# MARK.net
KiCad netlist of a schematic drawn in EAGLE
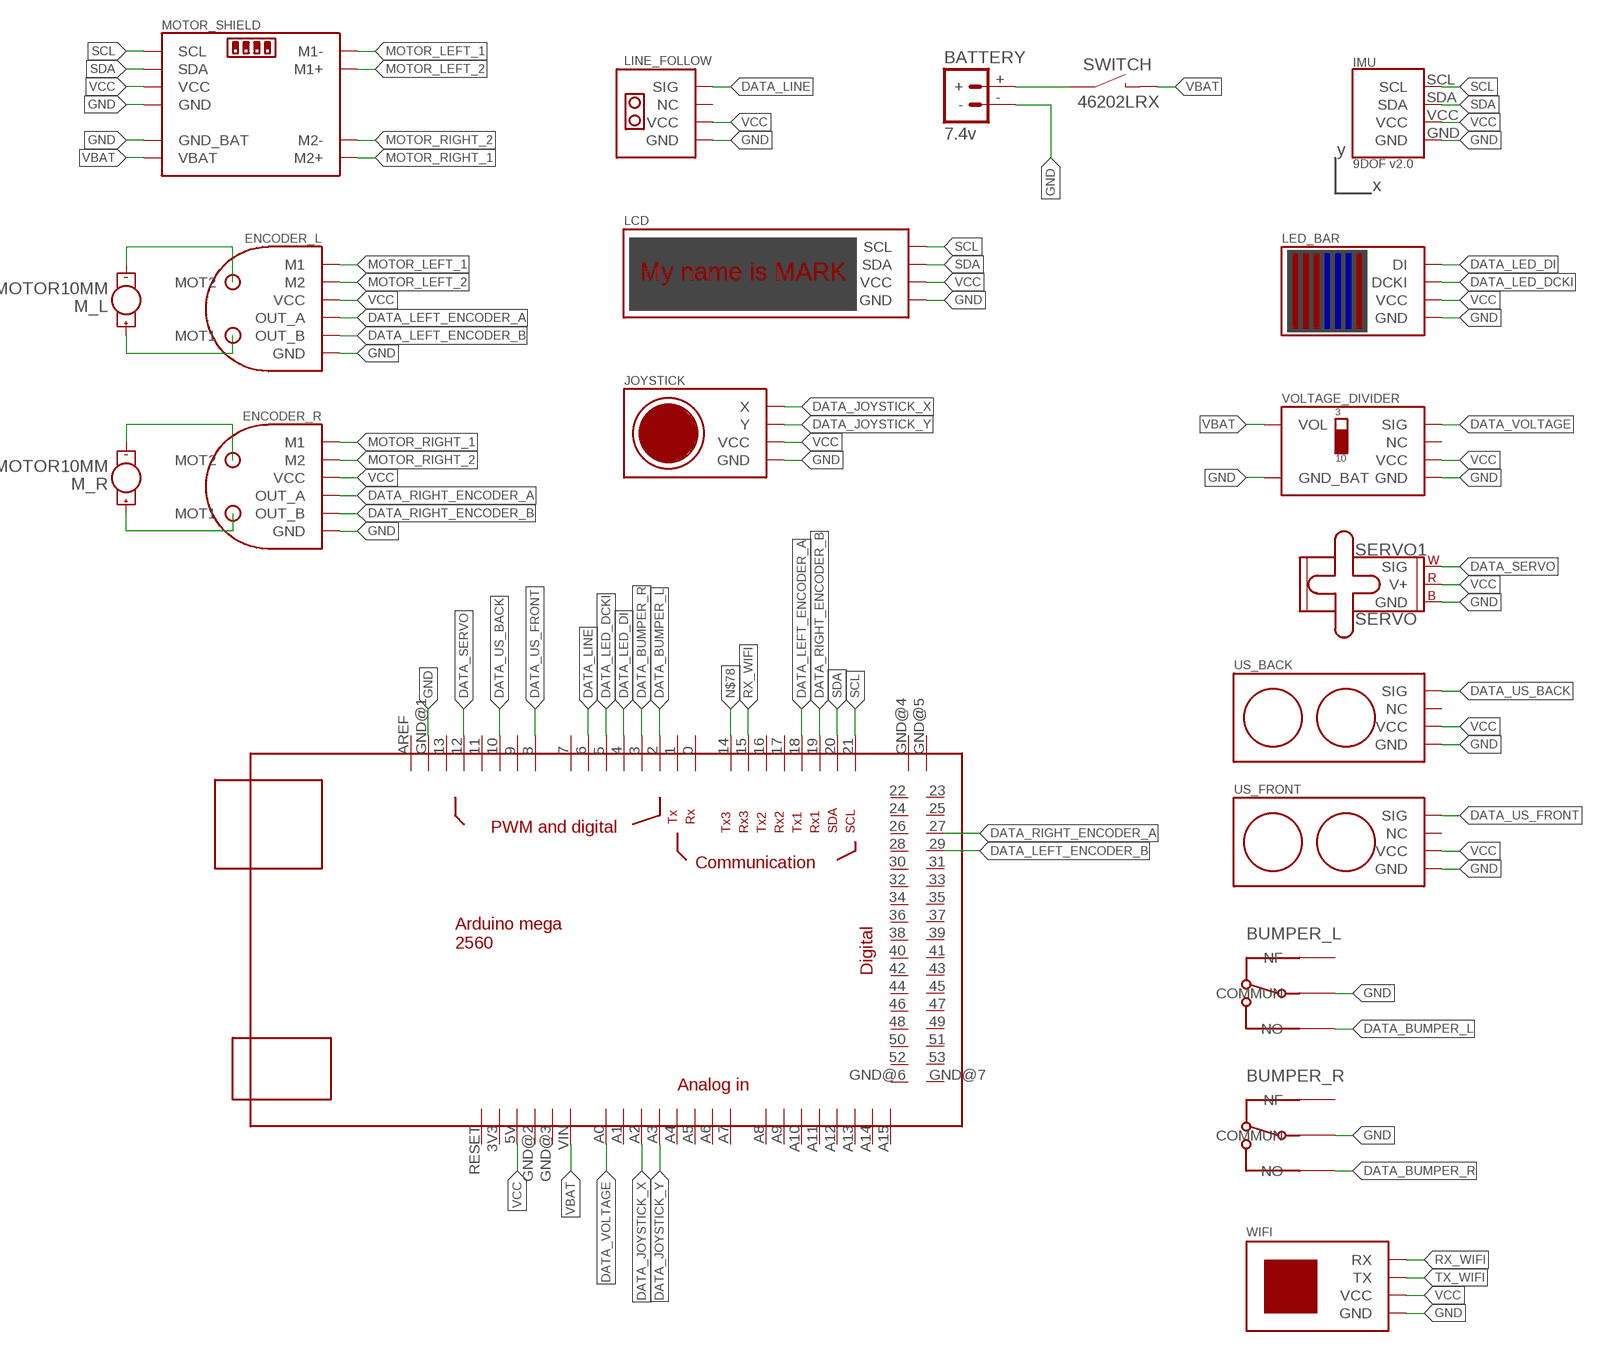
[diagram p0: schematic, sheet 1]

(export (version "E")
  (design (tool "Eeschema 10.0.6"))
  (components
    (comp (ref "BATTERY")
      (value "7.4v")
      (footprint "eagle-import:DEANS")
      (libsource (lib "eagle-import") (part "BATTERY_CONN_DEANS"))
    )
    (comp (ref "BUMPER_L")
      (value "MICROSWITCHCOUDE")
      (footprint "eagle-import:DG23-B3RA")
      (libsource (lib "eagle-import") (part "MICROSWITCHCOUDE"))
    )
    (comp (ref "BUMPER_R")
      (value "MICROSWITCHCOUDE")
      (footprint "eagle-import:DG23-B3RA")
      (libsource (lib "eagle-import") (part "MICROSWITCHCOUDE"))
    )
    (comp (ref "ENCODER_L")
      (value "MOTOR")
      (footprint "eagle-import:MOTOR")
      (libsource (lib "eagle-import") (part "MOTOR"))
    )
    (comp (ref "ENCODER_R")
      (value "MOTOR")
      (footprint "eagle-import:MOTOR")
      (libsource (lib "eagle-import") (part "MOTOR"))
    )
    (comp (ref "IMU")
      (value "IMU")
      (footprint "eagle-import:IMU")
      (libsource (lib "eagle-import") (part "IMU"))
    )
    (comp (ref "JOYSTICK")
      (value "JOYSTICK")
      (footprint "eagle-import:JOYSTICK")
      (libsource (lib "eagle-import") (part "JOYSTICK"))
    )
    (comp (ref "LCD")
      (value "LCD")
      (footprint "eagle-import:LCD")
      (libsource (lib "eagle-import") (part "LCD"))
    )
    (comp (ref "LED_BAR")
      (value "LED_BAR")
      (footprint "eagle-import:LED_BAR")
      (libsource (lib "eagle-import") (part "LED_BAR"))
    )
    (comp (ref "LINE_FOLLOW")
      (value "INFRARED")
      (footprint "eagle-import:INFRARED")
      (libsource (lib "eagle-import") (part "INFRARED"))
    )
    (comp (ref "MOTOR_SHIELD")
      (value "MOTOR_SHIELD")
      (footprint "eagle-import:MOTOR_SHIELD")
      (libsource (lib "eagle-import") (part "MOTOR_SHIELD"))
    )
    (comp (ref "M_L")
      (value "MOTOR10MM")
      (footprint "eagle-import:VIBE-MOTOR-10MM")
      (libsource (lib "eagle-import") (part "MOTOR10MM"))
    )
    (comp (ref "M_R")
      (value "MOTOR10MM")
      (footprint "eagle-import:VIBE-MOTOR-10MM")
      (libsource (lib "eagle-import") (part "MOTOR10MM"))
    )
    (comp (ref "SERVO1")
      (value "SERVO")
      (footprint "eagle-import:1X03")
      (libsource (lib "eagle-import") (part "SERVO"))
    )
    (comp (ref "SWITCH")
      (value "46202LRX")
      (footprint "eagle-import:46202LRX")
      (libsource (lib "eagle-import") (part "46202LRX"))
    )
    (comp (ref "U$11")
      (value "MEGA_DEVICE")
      (footprint "eagle-import:MEGAOUTLINE")
      (libsource (lib "eagle-import") (part "MEGA_DEVICE"))
    )
    (comp (ref "US_BACK")
      (value "ULTRASONIC")
      (footprint "eagle-import:ULTRASONIC")
      (libsource (lib "eagle-import") (part "ULTRASONIC"))
    )
    (comp (ref "US_FRONT")
      (value "ULTRASONIC")
      (footprint "eagle-import:ULTRASONIC")
      (libsource (lib "eagle-import") (part "ULTRASONIC"))
    )
    (comp (ref "VOLTAGE_DIVIDER")
      (value "VOLTAGE_DIVIDER")
      (footprint "eagle-import:VOLTAGE_DIVIDER")
      (libsource (lib "eagle-import") (part "VOLTAGE_DIVIDER"))
    )
    (comp (ref "WIFI")
      (value "WIFI")
      (footprint "eagle-import:WIFI")
      (libsource (lib "eagle-import") (part "WIFI"))
    )
  )
  (nets
    (net (code "1") (name "DATA_BUMPER_L") (class "Default")
      (node (ref "BUMPER_L") (pin "NO") (pinfunction "NO_NO") (pintype "bidirectional"))
      (node (ref "U$11") (pin "2") (pinfunction "2_2") (pintype "bidirectional"))
    )
    (net (code "2") (name "DATA_BUMPER_R") (class "Default")
      (node (ref "BUMPER_R") (pin "NO") (pinfunction "NO_NO") (pintype "bidirectional"))
      (node (ref "U$11") (pin "3") (pinfunction "3_3") (pintype "bidirectional"))
    )
    (net (code "3") (name "DATA_JOYSTICK_X") (class "Default")
      (node (ref "JOYSTICK") (pin "X") (pinfunction "X_X") (pintype "output"))
      (node (ref "U$11") (pin "A2") (pinfunction "A2_A2") (pintype "bidirectional"))
    )
    (net (code "4") (name "DATA_JOYSTICK_Y") (class "Default")
      (node (ref "JOYSTICK") (pin "Y") (pinfunction "Y_Y") (pintype "output"))
      (node (ref "U$11") (pin "A3") (pinfunction "A3_A3") (pintype "bidirectional"))
    )
    (net (code "5") (name "DATA_LED_DCKI") (class "Default")
      (node (ref "LED_BAR") (pin "DCKI") (pinfunction "DCKI_DCKI") (pintype "bidirectional"))
      (node (ref "U$11") (pin "5") (pinfunction "5_5") (pintype "bidirectional"))
    )
    (net (code "6") (name "DATA_LED_DI") (class "Default")
      (node (ref "LED_BAR") (pin "DI") (pinfunction "DI_DI") (pintype "bidirectional"))
      (node (ref "U$11") (pin "4") (pinfunction "4_4") (pintype "bidirectional"))
    )
    (net (code "7") (name "DATA_LEFT_ENCODER_A") (class "Default")
      (node (ref "ENCODER_L") (pin "OUT_A") (pinfunction "OUT_A_OUT_A") (pintype "bidirectional"))
      (node (ref "U$11") (pin "18") (pinfunction "18_18") (pintype "bidirectional"))
    )
    (net (code "8") (name "DATA_LEFT_ENCODER_B") (class "Default")
      (node (ref "ENCODER_L") (pin "OUT_B") (pinfunction "OUT_B_OUT_B") (pintype "bidirectional"))
      (node (ref "U$11") (pin "29") (pinfunction "29_29") (pintype "bidirectional"))
    )
    (net (code "9") (name "DATA_LINE") (class "Default")
      (node (ref "LINE_FOLLOW") (pin "SIG") (pinfunction "SIG_SIG") (pintype "bidirectional"))
      (node (ref "U$11") (pin "6") (pinfunction "6_6") (pintype "bidirectional"))
    )
    (net (code "10") (name "DATA_RIGHT_ENCODER_A") (class "Default")
      (node (ref "ENCODER_R") (pin "OUT_A") (pinfunction "OUT_A_OUT_A") (pintype "bidirectional"))
      (node (ref "U$11") (pin "27") (pinfunction "27_27") (pintype "bidirectional"))
    )
    (net (code "11") (name "DATA_RIGHT_ENCODER_B") (class "Default")
      (node (ref "ENCODER_R") (pin "OUT_B") (pinfunction "OUT_B_OUT_B") (pintype "bidirectional"))
      (node (ref "U$11") (pin "19") (pinfunction "19_19") (pintype "bidirectional"))
    )
    (net (code "12") (name "DATA_SERVO") (class "Default")
      (node (ref "SERVO1") (pin "1") (pinfunction "SIG_1") (pintype "bidirectional"))
      (node (ref "U$11") (pin "12") (pinfunction "12_12") (pintype "bidirectional"))
    )
    (net (code "13") (name "DATA_US_BACK") (class "Default")
      (node (ref "U$11") (pin "10") (pinfunction "10_10") (pintype "bidirectional"))
      (node (ref "US_BACK") (pin "SIG") (pinfunction "SIG_SIG") (pintype "bidirectional"))
    )
    (net (code "14") (name "DATA_US_FRONT") (class "Default")
      (node (ref "U$11") (pin "8") (pinfunction "8_8") (pintype "bidirectional"))
      (node (ref "US_FRONT") (pin "SIG") (pinfunction "SIG_SIG") (pintype "bidirectional"))
    )
    (net (code "15") (name "DATA_VOLTAGE") (class "Default")
      (node (ref "U$11") (pin "A0") (pinfunction "A0_A0") (pintype "bidirectional"))
      (node (ref "VOLTAGE_DIVIDER") (pin "3") (pinfunction "SIG_3") (pintype "bidirectional"))
    )
    (net (code "16") (name "GND") (class "Default")
      (node (ref "BATTERY") (pin "-") (pinfunction "-_-") (pintype "passive"))
      (node (ref "BUMPER_L") (pin "COMMUN") (pinfunction "COMMUN_COMMUN") (pintype "bidirectional"))
      (node (ref "BUMPER_R") (pin "COMMUN") (pinfunction "COMMUN_COMMUN") (pintype "bidirectional"))
      (node (ref "ENCODER_L") (pin "GND") (pinfunction "GND_GND") (pintype "bidirectional"))
      (node (ref "ENCODER_R") (pin "GND") (pinfunction "GND_GND") (pintype "bidirectional"))
      (node (ref "IMU") (pin "GND") (pinfunction "GND_GND") (pintype "bidirectional"))
      (node (ref "JOYSTICK") (pin "GND") (pinfunction "GND_GND") (pintype "power_in"))
      (node (ref "LCD") (pin "GND") (pinfunction "GND_GND") (pintype "bidirectional"))
      (node (ref "LED_BAR") (pin "GND") (pinfunction "GND_GND") (pintype "bidirectional"))
      (node (ref "LINE_FOLLOW") (pin "GND") (pinfunction "GND_GND") (pintype "bidirectional"))
      (node (ref "MOTOR_SHIELD") (pin "GND") (pinfunction "GND_GND") (pintype "bidirectional"))
      (node (ref "MOTOR_SHIELD") (pin "GND_BAT") (pinfunction "GND_BAT_GND_BAT") (pintype "bidirectional"))
      (node (ref "SERVO1") (pin "3") (pinfunction "GND_3") (pintype "bidirectional"))
      (node (ref "U$11") (pin "GND@1") (pinfunction "GND_GND@1") (pintype "bidirectional"))
      (node (ref "US_BACK") (pin "GND") (pinfunction "GND_GND") (pintype "bidirectional"))
      (node (ref "US_FRONT") (pin "GND") (pinfunction "GND_GND") (pintype "bidirectional"))
      (node (ref "VOLTAGE_DIVIDER") (pin "2") (pinfunction "GND_BAT_2") (pintype "bidirectional"))
      (node (ref "VOLTAGE_DIVIDER") (pin "6") (pinfunction "GND_6") (pintype "bidirectional"))
      (node (ref "WIFI") (pin "GND") (pinfunction "GND_GND") (pintype "bidirectional"))
    )
    (net (code "17") (name "MOTOR_LEFT_1") (class "Default")
      (node (ref "ENCODER_L") (pin "M1") (pinfunction "M1_M1") (pintype "bidirectional"))
      (node (ref "MOTOR_SHIELD") (pin "M1-") (pinfunction "M1-_M1-") (pintype "bidirectional"))
    )
    (net (code "18") (name "MOTOR_LEFT_2") (class "Default")
      (node (ref "ENCODER_L") (pin "M2") (pinfunction "M2_M2") (pintype "bidirectional"))
      (node (ref "MOTOR_SHIELD") (pin "M1+") (pinfunction "M1+_M1+") (pintype "bidirectional"))
    )
    (net (code "19") (name "MOTOR_RIGHT_1") (class "Default")
      (node (ref "ENCODER_R") (pin "M1") (pinfunction "M1_M1") (pintype "bidirectional"))
      (node (ref "MOTOR_SHIELD") (pin "M2+") (pinfunction "M2+_M2+") (pintype "bidirectional"))
    )
    (net (code "20") (name "MOTOR_RIGHT_2") (class "Default")
      (node (ref "ENCODER_R") (pin "M2") (pinfunction "M2_M2") (pintype "bidirectional"))
      (node (ref "MOTOR_SHIELD") (pin "M2-") (pinfunction "M2-_M2-") (pintype "bidirectional"))
    )
    (net (code "21") (name "N$78") (class "Default")
      (node (ref "U$11") (pin "14") (pinfunction "14_14") (pintype "bidirectional"))
    )
    (net (code "22") (name "Net-(ENCODER_L-PadMOT1)") (class "Default")
      (node (ref "ENCODER_L") (pin "MOT1") (pinfunction "MOT1_MOT1") (pintype "bidirectional"))
      (node (ref "M_L") (pin "+") (pinfunction "+_+") (pintype "bidirectional"))
    )
    (net (code "23") (name "Net-(ENCODER_L-PadMOT2)") (class "Default")
      (node (ref "ENCODER_L") (pin "MOT2") (pinfunction "MOT2_MOT2") (pintype "bidirectional"))
      (node (ref "M_L") (pin "-") (pinfunction "-_-") (pintype "bidirectional"))
    )
    (net (code "24") (name "Net-(ENCODER_R-PadMOT1)") (class "Default")
      (node (ref "ENCODER_R") (pin "MOT1") (pinfunction "MOT1_MOT1") (pintype "bidirectional"))
      (node (ref "M_R") (pin "+") (pinfunction "+_+") (pintype "bidirectional"))
    )
    (net (code "25") (name "Net-(ENCODER_R-PadMOT2)") (class "Default")
      (node (ref "ENCODER_R") (pin "MOT2") (pinfunction "MOT2_MOT2") (pintype "bidirectional"))
      (node (ref "M_R") (pin "-") (pinfunction "-_-") (pintype "bidirectional"))
    )
    (net (code "26") (name "Net-(SWITCH-A1)") (class "Default")
      (node (ref "BATTERY") (pin "+") (pinfunction "+_+") (pintype "passive"))
      (node (ref "SWITCH") (pin "P$1") (pinfunction "A1_P$1") (pintype "passive"))
    )
    (net (code "27") (name "RX_WIFI") (class "Default")
      (node (ref "U$11") (pin "15") (pinfunction "15_15") (pintype "bidirectional"))
      (node (ref "WIFI") (pin "RX") (pinfunction "RX_RX") (pintype "bidirectional"))
    )
    (net (code "28") (name "SCL") (class "Default")
      (node (ref "IMU") (pin "SCL") (pinfunction "SCL_SCL") (pintype "bidirectional"))
      (node (ref "LCD") (pin "SCL") (pinfunction "SCL_SCL") (pintype "bidirectional"))
      (node (ref "MOTOR_SHIELD") (pin "SCL") (pinfunction "SCL_SCL") (pintype "bidirectional"))
      (node (ref "U$11") (pin "21") (pinfunction "21_21") (pintype "bidirectional"))
    )
    (net (code "29") (name "SDA") (class "Default")
      (node (ref "IMU") (pin "SDA") (pinfunction "SDA_SDA") (pintype "bidirectional"))
      (node (ref "LCD") (pin "SDA") (pinfunction "SDA_SDA") (pintype "bidirectional"))
      (node (ref "MOTOR_SHIELD") (pin "SDA") (pinfunction "SDA_SDA") (pintype "bidirectional"))
      (node (ref "U$11") (pin "20") (pinfunction "20_20") (pintype "bidirectional"))
    )
    (net (code "30") (name "TX_WIFI") (class "Default")
      (node (ref "WIFI") (pin "TX") (pinfunction "TX_TX") (pintype "bidirectional"))
    )
    (net (code "31") (name "VBAT") (class "Default")
      (node (ref "MOTOR_SHIELD") (pin "VBAT") (pinfunction "VBAT_VBAT") (pintype "bidirectional"))
      (node (ref "SWITCH") (pin "P$2") (pinfunction "B_P$2") (pintype "passive"))
      (node (ref "U$11") (pin "VIN") (pinfunction "VIN_VIN") (pintype "bidirectional"))
      (node (ref "VOLTAGE_DIVIDER") (pin "1") (pinfunction "VOL_1") (pintype "bidirectional"))
    )
    (net (code "32") (name "VCC") (class "Default")
      (node (ref "ENCODER_L") (pin "VCC") (pinfunction "VCC_VCC") (pintype "bidirectional"))
      (node (ref "ENCODER_R") (pin "VCC") (pinfunction "VCC_VCC") (pintype "bidirectional"))
      (node (ref "IMU") (pin "VCC") (pinfunction "VCC_VCC") (pintype "bidirectional"))
      (node (ref "JOYSTICK") (pin "VCC") (pinfunction "VCC_VCC") (pintype "power_in"))
      (node (ref "LCD") (pin "VCC") (pinfunction "VCC_VCC") (pintype "bidirectional"))
      (node (ref "LED_BAR") (pin "VCC") (pinfunction "VCC_VCC") (pintype "bidirectional"))
      (node (ref "LINE_FOLLOW") (pin "VCC") (pinfunction "VCC_VCC") (pintype "bidirectional"))
      (node (ref "MOTOR_SHIELD") (pin "VCC") (pinfunction "VCC_VCC") (pintype "bidirectional"))
      (node (ref "SERVO1") (pin "2") (pinfunction "V+_2") (pintype "bidirectional"))
      (node (ref "U$11") (pin "5V") (pinfunction "5V_5V") (pintype "bidirectional"))
      (node (ref "US_BACK") (pin "VCC") (pinfunction "VCC_VCC") (pintype "bidirectional"))
      (node (ref "US_FRONT") (pin "VCC") (pinfunction "VCC_VCC") (pintype "bidirectional"))
      (node (ref "VOLTAGE_DIVIDER") (pin "5") (pinfunction "VCC_5") (pintype "bidirectional"))
      (node (ref "WIFI") (pin "VCC") (pinfunction "VCC_VCC") (pintype "bidirectional"))
    )
    (net (code "33") (name "unconnected-(BUMPER_L-PadNF)") (class "Default")
      (node (ref "BUMPER_L") (pin "NF") (pinfunction "NF_NF") (pintype "bidirectional"))
    )
    (net (code "34") (name "unconnected-(BUMPER_R-PadNF)") (class "Default")
      (node (ref "BUMPER_R") (pin "NF") (pinfunction "NF_NF") (pintype "bidirectional"))
    )
    (net (code "35") (name "unconnected-(LINE_FOLLOW-PadNC)") (class "Default")
      (node (ref "LINE_FOLLOW") (pin "NC") (pinfunction "NC_NC") (pintype "bidirectional"))
    )
    (net (code "36") (name "unconnected-(U$11-GND-PadGND@2)") (class "Default")
      (node (ref "U$11") (pin "GND@2") (pinfunction "GND_GND@2") (pintype "bidirectional"))
    )
    (net (code "37") (name "unconnected-(U$11-GND-PadGND@3)") (class "Default")
      (node (ref "U$11") (pin "GND@3") (pinfunction "GND_GND@3") (pintype "bidirectional"))
    )
    (net (code "38") (name "unconnected-(U$11-GND-PadGND@4)") (class "Default")
      (node (ref "U$11") (pin "GND@4") (pinfunction "GND_GND@4") (pintype "bidirectional"))
    )
    (net (code "39") (name "unconnected-(U$11-GND-PadGND@5)") (class "Default")
      (node (ref "U$11") (pin "GND@5") (pinfunction "GND_GND@5") (pintype "bidirectional"))
    )
    (net (code "40") (name "unconnected-(U$11-GND-PadGND@6)") (class "Default")
      (node (ref "U$11") (pin "GND@6") (pinfunction "GND_GND@6") (pintype "bidirectional"))
    )
    (net (code "41") (name "unconnected-(U$11-GND-PadGND@7)") (class "Default")
      (node (ref "U$11") (pin "GND@7") (pinfunction "GND_GND@7") (pintype "bidirectional"))
    )
    (net (code "42") (name "unconnected-(U$11-Pad0)") (class "Default")
      (node (ref "U$11") (pin "0") (pinfunction "0_0") (pintype "bidirectional"))
    )
    (net (code "43") (name "unconnected-(U$11-Pad1)") (class "Default")
      (node (ref "U$11") (pin "1") (pinfunction "1_1") (pintype "bidirectional"))
    )
    (net (code "44") (name "unconnected-(U$11-Pad3V3)") (class "Default")
      (node (ref "U$11") (pin "3V3") (pinfunction "3V3_3V3") (pintype "bidirectional"))
    )
    (net (code "45") (name "unconnected-(U$11-Pad7)") (class "Default")
      (node (ref "U$11") (pin "7") (pinfunction "7_7") (pintype "bidirectional"))
    )
    (net (code "46") (name "unconnected-(U$11-Pad9)") (class "Default")
      (node (ref "U$11") (pin "9") (pinfunction "9_9") (pintype "bidirectional"))
    )
    (net (code "47") (name "unconnected-(U$11-Pad11)") (class "Default")
      (node (ref "U$11") (pin "11") (pinfunction "11_11") (pintype "bidirectional"))
    )
    (net (code "48") (name "unconnected-(U$11-Pad13)") (class "Default")
      (node (ref "U$11") (pin "13") (pinfunction "13_13") (pintype "bidirectional"))
    )
    (net (code "49") (name "unconnected-(U$11-Pad16)") (class "Default")
      (node (ref "U$11") (pin "16") (pinfunction "16_16") (pintype "bidirectional"))
    )
    (net (code "50") (name "unconnected-(U$11-Pad17)") (class "Default")
      (node (ref "U$11") (pin "17") (pinfunction "17_17") (pintype "bidirectional"))
    )
    (net (code "51") (name "unconnected-(U$11-Pad22)") (class "Default")
      (node (ref "U$11") (pin "22") (pinfunction "22_22") (pintype "bidirectional"))
    )
    (net (code "52") (name "unconnected-(U$11-Pad23)") (class "Default")
      (node (ref "U$11") (pin "23") (pinfunction "23_23") (pintype "bidirectional"))
    )
    (net (code "53") (name "unconnected-(U$11-Pad24)") (class "Default")
      (node (ref "U$11") (pin "24") (pinfunction "24_24") (pintype "bidirectional"))
    )
    (net (code "54") (name "unconnected-(U$11-Pad25)") (class "Default")
      (node (ref "U$11") (pin "25") (pinfunction "25_25") (pintype "bidirectional"))
    )
    (net (code "55") (name "unconnected-(U$11-Pad26)") (class "Default")
      (node (ref "U$11") (pin "26") (pinfunction "26_26") (pintype "bidirectional"))
    )
    (net (code "56") (name "unconnected-(U$11-Pad28)") (class "Default")
      (node (ref "U$11") (pin "28") (pinfunction "28_28") (pintype "bidirectional"))
    )
    (net (code "57") (name "unconnected-(U$11-Pad30)") (class "Default")
      (node (ref "U$11") (pin "30") (pinfunction "30_30") (pintype "bidirectional"))
    )
    (net (code "58") (name "unconnected-(U$11-Pad31)") (class "Default")
      (node (ref "U$11") (pin "31") (pinfunction "31_31") (pintype "bidirectional"))
    )
    (net (code "59") (name "unconnected-(U$11-Pad32)") (class "Default")
      (node (ref "U$11") (pin "32") (pinfunction "32_32") (pintype "bidirectional"))
    )
    (net (code "60") (name "unconnected-(U$11-Pad33)") (class "Default")
      (node (ref "U$11") (pin "33") (pinfunction "33_33") (pintype "bidirectional"))
    )
    (net (code "61") (name "unconnected-(U$11-Pad34)") (class "Default")
      (node (ref "U$11") (pin "34") (pinfunction "34_34") (pintype "bidirectional"))
    )
    (net (code "62") (name "unconnected-(U$11-Pad35)") (class "Default")
      (node (ref "U$11") (pin "35") (pinfunction "35_35") (pintype "bidirectional"))
    )
    (net (code "63") (name "unconnected-(U$11-Pad36)") (class "Default")
      (node (ref "U$11") (pin "36") (pinfunction "36_36") (pintype "bidirectional"))
    )
    (net (code "64") (name "unconnected-(U$11-Pad37)") (class "Default")
      (node (ref "U$11") (pin "37") (pinfunction "37_37") (pintype "bidirectional"))
    )
    (net (code "65") (name "unconnected-(U$11-Pad38)") (class "Default")
      (node (ref "U$11") (pin "38") (pinfunction "38_38") (pintype "bidirectional"))
    )
    (net (code "66") (name "unconnected-(U$11-Pad39)") (class "Default")
      (node (ref "U$11") (pin "39") (pinfunction "39_39") (pintype "bidirectional"))
    )
    (net (code "67") (name "unconnected-(U$11-Pad40)") (class "Default")
      (node (ref "U$11") (pin "40") (pinfunction "40_40") (pintype "bidirectional"))
    )
    (net (code "68") (name "unconnected-(U$11-Pad41)") (class "Default")
      (node (ref "U$11") (pin "41") (pinfunction "41_41") (pintype "bidirectional"))
    )
    (net (code "69") (name "unconnected-(U$11-Pad42)") (class "Default")
      (node (ref "U$11") (pin "42") (pinfunction "42_42") (pintype "bidirectional"))
    )
    (net (code "70") (name "unconnected-(U$11-Pad43)") (class "Default")
      (node (ref "U$11") (pin "43") (pinfunction "43_43") (pintype "bidirectional"))
    )
    (net (code "71") (name "unconnected-(U$11-Pad44)") (class "Default")
      (node (ref "U$11") (pin "44") (pinfunction "44_44") (pintype "bidirectional"))
    )
    (net (code "72") (name "unconnected-(U$11-Pad45)") (class "Default")
      (node (ref "U$11") (pin "45") (pinfunction "45_45") (pintype "bidirectional"))
    )
    (net (code "73") (name "unconnected-(U$11-Pad46)") (class "Default")
      (node (ref "U$11") (pin "46") (pinfunction "46_46") (pintype "bidirectional"))
    )
    (net (code "74") (name "unconnected-(U$11-Pad47)") (class "Default")
      (node (ref "U$11") (pin "47") (pinfunction "47_47") (pintype "bidirectional"))
    )
    (net (code "75") (name "unconnected-(U$11-Pad48)") (class "Default")
      (node (ref "U$11") (pin "48") (pinfunction "48_48") (pintype "bidirectional"))
    )
    (net (code "76") (name "unconnected-(U$11-Pad49)") (class "Default")
      (node (ref "U$11") (pin "49") (pinfunction "49_49") (pintype "bidirectional"))
    )
    (net (code "77") (name "unconnected-(U$11-Pad50)") (class "Default")
      (node (ref "U$11") (pin "50") (pinfunction "50_50") (pintype "bidirectional"))
    )
    (net (code "78") (name "unconnected-(U$11-Pad51)") (class "Default")
      (node (ref "U$11") (pin "51") (pinfunction "51_51") (pintype "bidirectional"))
    )
    (net (code "79") (name "unconnected-(U$11-Pad52)") (class "Default")
      (node (ref "U$11") (pin "52") (pinfunction "52_52") (pintype "bidirectional"))
    )
    (net (code "80") (name "unconnected-(U$11-Pad53)") (class "Default")
      (node (ref "U$11") (pin "53") (pinfunction "53_53") (pintype "bidirectional"))
    )
    (net (code "81") (name "unconnected-(U$11-PadA1)") (class "Default")
      (node (ref "U$11") (pin "A1") (pinfunction "A1_A1") (pintype "bidirectional"))
    )
    (net (code "82") (name "unconnected-(U$11-PadA4)") (class "Default")
      (node (ref "U$11") (pin "A4") (pinfunction "A4_A4") (pintype "bidirectional"))
    )
    (net (code "83") (name "unconnected-(U$11-PadA5)") (class "Default")
      (node (ref "U$11") (pin "A5") (pinfunction "A5_A5") (pintype "bidirectional"))
    )
    (net (code "84") (name "unconnected-(U$11-PadA6)") (class "Default")
      (node (ref "U$11") (pin "A6") (pinfunction "A6_A6") (pintype "bidirectional"))
    )
    (net (code "85") (name "unconnected-(U$11-PadA7)") (class "Default")
      (node (ref "U$11") (pin "A7") (pinfunction "A7_A7") (pintype "bidirectional"))
    )
    (net (code "86") (name "unconnected-(U$11-PadA8)") (class "Default")
      (node (ref "U$11") (pin "A8") (pinfunction "A8_A8") (pintype "bidirectional"))
    )
    (net (code "87") (name "unconnected-(U$11-PadA9)") (class "Default")
      (node (ref "U$11") (pin "A9") (pinfunction "A9_A9") (pintype "bidirectional"))
    )
    (net (code "88") (name "unconnected-(U$11-PadA10)") (class "Default")
      (node (ref "U$11") (pin "A10") (pinfunction "A10_A10") (pintype "bidirectional"))
    )
    (net (code "89") (name "unconnected-(U$11-PadA11)") (class "Default")
      (node (ref "U$11") (pin "A11") (pinfunction "A11_A11") (pintype "bidirectional"))
    )
    (net (code "90") (name "unconnected-(U$11-PadA12)") (class "Default")
      (node (ref "U$11") (pin "A12") (pinfunction "A12_A12") (pintype "bidirectional"))
    )
    (net (code "91") (name "unconnected-(U$11-PadA13)") (class "Default")
      (node (ref "U$11") (pin "A13") (pinfunction "A13_A13") (pintype "bidirectional"))
    )
    (net (code "92") (name "unconnected-(U$11-PadA14)") (class "Default")
      (node (ref "U$11") (pin "A14") (pinfunction "A14_A14") (pintype "bidirectional"))
    )
    (net (code "93") (name "unconnected-(U$11-PadA15)") (class "Default")
      (node (ref "U$11") (pin "A15") (pinfunction "A15_A15") (pintype "bidirectional"))
    )
    (net (code "94") (name "unconnected-(U$11-PadAREF)") (class "Default")
      (node (ref "U$11") (pin "AREF") (pinfunction "AREF_AREF") (pintype "bidirectional"))
    )
    (net (code "95") (name "unconnected-(U$11-PadRESET)") (class "Default")
      (node (ref "U$11") (pin "RESET") (pinfunction "RESET_RESET") (pintype "bidirectional"))
    )
    (net (code "96") (name "unconnected-(US_BACK-PadNC)") (class "Default")
      (node (ref "US_BACK") (pin "NC") (pinfunction "NC_NC") (pintype "bidirectional"))
    )
    (net (code "97") (name "unconnected-(US_FRONT-PadNC)") (class "Default")
      (node (ref "US_FRONT") (pin "NC") (pinfunction "NC_NC") (pintype "bidirectional"))
    )
    (net (code "98") (name "unconnected-(VOLTAGE_DIVIDER-NC-Pad4)") (class "Default")
      (node (ref "VOLTAGE_DIVIDER") (pin "4") (pinfunction "NC_4") (pintype "bidirectional"))
    )
  )
)
